# LG6.net
KiCad netlist of a schematic drawn in Altium Designer
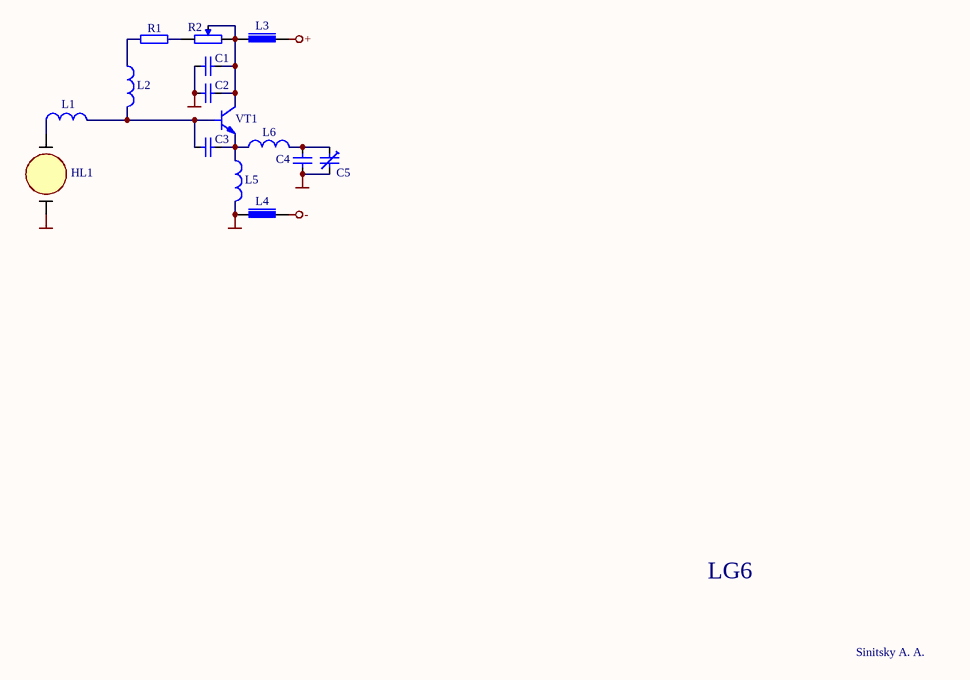
[diagram p0: LG6.SchDoc]

(export (version "E")
  (design (tool "Eeschema 10.0.6"))
  (components
    (comp (ref "C1")
      (value "CER")
      (footprint "C_0805_0.9")
      (description "Capacitor")
      (libsource (lib "Resistors_Capacitors") (part "C_Ceramic"))
    )
    (comp (ref "C2")
      (value "CER")
      (footprint "C_0805_0.6")
      (description "Capacitor")
      (libsource (lib "Resistors_Capacitors") (part "C_Ceramic"))
    )
    (comp (ref "C3")
      (value "CER")
      (footprint "C_0805_0.6")
      (description "Capacitor")
      (libsource (lib "Resistors_Capacitors") (part "C_Ceramic"))
    )
    (comp (ref "C4")
      (value "CER")
      (footprint "C_0805_0.6")
      (description "Capacitor")
      (libsource (lib "Resistors_Capacitors") (part "C_Ceramic"))
    )
    (comp (ref "C5")
      (value "C_Trimmer")
      (footprint "TZB4-B")
      (description "Capacitor")
      (libsource (lib "Resistors_Capacitors") (part "C_Trimmer"))
    )
    (comp (ref "HL1")
      (value "CE_Lamp")
      (description "Capacitive Excitation Gas Discharge Lamp")
      (libsource (lib "Special") (part "CE_Lamp"))
    )
    (comp (ref "L1")
      (value "Inductor_1")
      (description "Coreless Inductor")
      (libsource (lib "Inductive") (part "Inductor_1"))
    )
    (comp (ref "L2")
      (value "Inductor_1")
      (footprint "L_1210_2")
      (description "Coreless Inductor")
      (libsource (lib "Inductive") (part "Inductor_1"))
    )
    (comp (ref "L3")
      (value "EMI_Suppressor")
      (footprint "L_1206_1.25")
      (description "Inductive EMI Suppressor")
      (libsource (lib "Inductive") (part "EMI_Suppressor"))
    )
    (comp (ref "L4")
      (value "EMI_Suppressor")
      (footprint "L_1206_1.25")
      (description "Inductive EMI Suppressor")
      (libsource (lib "Inductive") (part "EMI_Suppressor"))
    )
    (comp (ref "L5")
      (value "Inductor_1")
      (footprint "L_1210_2")
      (description "Coreless Inductor")
      (libsource (lib "Inductive") (part "Inductor_1"))
    )
    (comp (ref "L6")
      (value "Inductor_1")
      (footprint "L_1210_2")
      (description "Coreless Inductor")
      (libsource (lib "Inductive") (part "Inductor_1"))
    )
    (comp (ref "R1")
      (value "Resistor")
      (footprint "R_0805")
      (description "Constant")
      (libsource (lib "Resistors") (part "Resistor"))
    )
    (comp (ref "R2")
      (value "R_Variable")
      (footprint "RJ50")
      (description "Resistor")
      (libsource (lib "Resistors_Capacitors") (part "R_Variable"))
    )
    (comp (ref "VT1")
      (value "1_NPN_SOT89")
      (footprint "SOT-89")
      (libsource (lib "Semiconductors") (part "1_NPN_SOT89"))
    )
  )
  (nets
    (net (code "1") (name "+") (class "Default")
      (node (ref "L3") (pin "2") (pinfunction "2_2") (pintype "passive"))
    )
    (net (code "2") (name "-") (class "Default")
      (node (ref "L4") (pin "2") (pinfunction "2_2") (pintype "passive"))
    )
    (net (code "3") (name "GND") (class "Default")
      (node (ref "C1") (pin "1") (pinfunction "1_1") (pintype "passive"))
      (node (ref "C2") (pin "1") (pinfunction "1_1") (pintype "passive"))
      (node (ref "C4") (pin "1") (pinfunction "1_1") (pintype "passive"))
      (node (ref "C5") (pin "1") (pinfunction "1_1") (pintype "passive"))
      (node (ref "HL1") (pin "2") (pinfunction "2_2") (pintype "passive"))
      (node (ref "L4") (pin "1") (pinfunction "1_1") (pintype "passive"))
      (node (ref "L5") (pin "2") (pinfunction "2_2") (pintype "passive"))
    )
    (net (code "4") (name "Net-(C4-Pad2)") (class "Default")
      (node (ref "C4") (pin "2") (pinfunction "2_2") (pintype "passive"))
      (node (ref "C5") (pin "2") (pinfunction "2_2") (pintype "passive"))
      (node (ref "L6") (pin "2") (pinfunction "2_2") (pintype "passive"))
    )
    (net (code "5") (name "Net-(HL1-Pad1)") (class "Default")
      (node (ref "HL1") (pin "1") (pinfunction "1_1") (pintype "passive"))
      (node (ref "L1") (pin "1") (pinfunction "1_1") (pintype "passive"))
    )
    (net (code "6") (name "Net-(L2-Pad1)") (class "Default")
      (node (ref "L2") (pin "1") (pinfunction "1_1") (pintype "passive"))
      (node (ref "R1") (pin "2") (pinfunction "2_2") (pintype "passive"))
    )
    (net (code "7") (name "Net-(R1-Pad1)") (class "Default")
      (node (ref "R1") (pin "1") (pinfunction "1_1") (pintype "passive"))
      (node (ref "R2") (pin "3") (pinfunction "3_3") (pintype "passive"))
    )
    (net (code "8") (name "Net-(VT1-B)") (class "Default")
      (node (ref "C3") (pin "1") (pinfunction "1_1") (pintype "passive"))
      (node (ref "L1") (pin "2") (pinfunction "2_2") (pintype "passive"))
      (node (ref "L2") (pin "2") (pinfunction "2_2") (pintype "passive"))
      (node (ref "VT1") (pin "1") (pinfunction "B_1") (pintype "passive"))
    )
    (net (code "9") (name "Net-(VT1-C)") (class "Default")
      (node (ref "C1") (pin "2") (pinfunction "2_2") (pintype "passive"))
      (node (ref "C2") (pin "2") (pinfunction "2_2") (pintype "passive"))
      (node (ref "L3") (pin "1") (pinfunction "1_1") (pintype "passive"))
      (node (ref "R2") (pin "1") (pinfunction "1_1") (pintype "passive"))
      (node (ref "R2") (pin "2") (pinfunction "2_2") (pintype "passive"))
      (node (ref "VT1") (pin "2") (pinfunction "C_2") (pintype "passive"))
    )
    (net (code "10") (name "Net-(VT1-E)") (class "Default")
      (node (ref "C3") (pin "2") (pinfunction "2_2") (pintype "passive"))
      (node (ref "L5") (pin "1") (pinfunction "1_1") (pintype "passive"))
      (node (ref "L6") (pin "1") (pinfunction "1_1") (pintype "passive"))
      (node (ref "VT1") (pin "3") (pinfunction "E_3") (pintype "passive"))
    )
  )
)
